# Solenoid_and_Flasher_Driver.net
KiCad netlist of a schematic drawn in Altium Designer
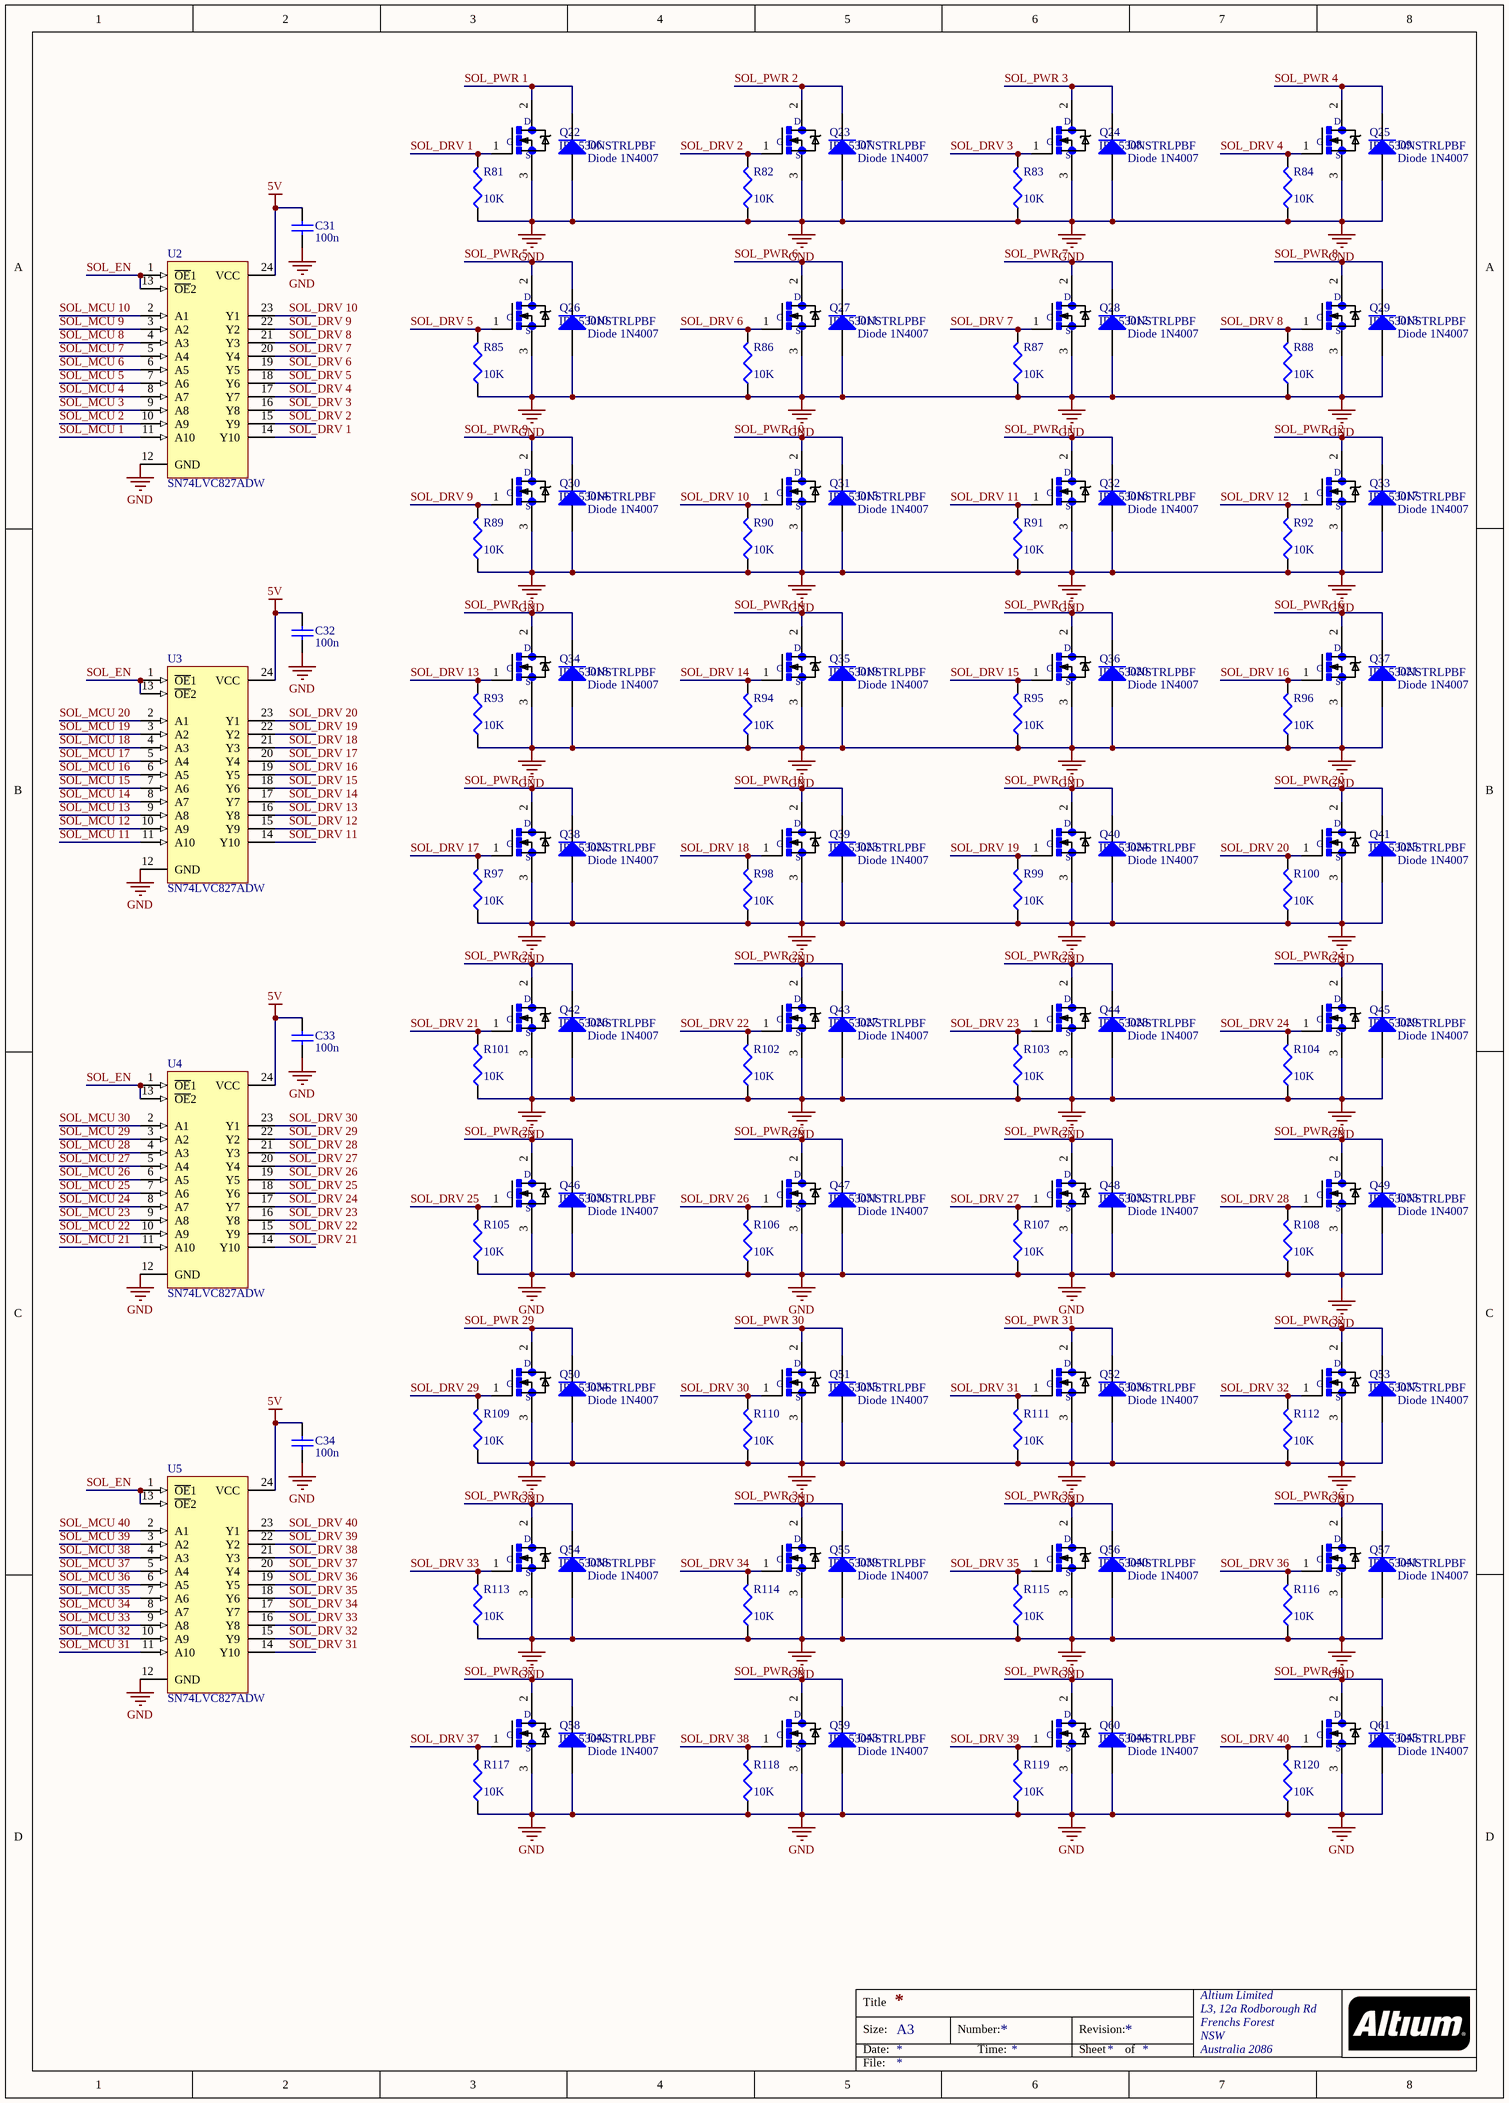
[diagram p0: Solenoid and Flasher Driver.SchDoc]

(export (version "E")
  (design (tool "Eeschema 10.0.6"))
  (components
    (comp (ref "C31")
      (value "100n")
      (footprint "0805C-GENERIC")
      (description "Capacitor (Semiconductor SIM Model)")
      (fields (field (name "Comment") "Cap Semi") (field (name "PUBLISHER") "Altium Limited"))
      (libsource (lib "Miscellaneous Devices") (part "Cap Semi"))
    )
    (comp (ref "C32")
      (value "100n")
      (footprint "0805C-GENERIC")
      (description "Capacitor (Semiconductor SIM Model)")
      (fields (field (name "Comment") "Cap Semi") (field (name "PUBLISHER") "Altium Limited"))
      (libsource (lib "Miscellaneous Devices") (part "Cap Semi"))
    )
    (comp (ref "C33")
      (value "100n")
      (footprint "0805C-GENERIC")
      (description "Capacitor (Semiconductor SIM Model)")
      (fields (field (name "Comment") "Cap Semi") (field (name "PUBLISHER") "Altium Limited"))
      (libsource (lib "Miscellaneous Devices") (part "Cap Semi"))
    )
    (comp (ref "C34")
      (value "100n")
      (footprint "0805C-GENERIC")
      (description "Capacitor (Semiconductor SIM Model)")
      (fields (field (name "Comment") "Cap Semi") (field (name "PUBLISHER") "Altium Limited"))
      (libsource (lib "Miscellaneous Devices") (part "Cap Semi"))
    )
    (comp (ref "D6")
      (value "Diode 1N4007")
      (footprint "DO-41")
      (description "1 Amp General Purpose Rectifier")
      (fields (field (name "PUBLISHER") "Altium Limited"))
      (libsource (lib "Miscellaneous Devices") (part "Diode 1N4007"))
    )
    (comp (ref "D7")
      (value "Diode 1N4007")
      (footprint "DO-41")
      (description "1 Amp General Purpose Rectifier")
      (fields (field (name "PUBLISHER") "Altium Limited"))
      (libsource (lib "Miscellaneous Devices") (part "Diode 1N4007"))
    )
    (comp (ref "D8")
      (value "Diode 1N4007")
      (footprint "DO-41")
      (description "1 Amp General Purpose Rectifier")
      (fields (field (name "PUBLISHER") "Altium Limited"))
      (libsource (lib "Miscellaneous Devices") (part "Diode 1N4007"))
    )
    (comp (ref "D9")
      (value "Diode 1N4007")
      (footprint "DO-41")
      (description "1 Amp General Purpose Rectifier")
      (fields (field (name "PUBLISHER") "Altium Limited"))
      (libsource (lib "Miscellaneous Devices") (part "Diode 1N4007"))
    )
    (comp (ref "D10")
      (value "Diode 1N4007")
      (footprint "DO-41")
      (description "1 Amp General Purpose Rectifier")
      (fields (field (name "PUBLISHER") "Altium Limited"))
      (libsource (lib "Miscellaneous Devices") (part "Diode 1N4007"))
    )
    (comp (ref "D11")
      (value "Diode 1N4007")
      (footprint "DO-41")
      (description "1 Amp General Purpose Rectifier")
      (fields (field (name "PUBLISHER") "Altium Limited"))
      (libsource (lib "Miscellaneous Devices") (part "Diode 1N4007"))
    )
    (comp (ref "D12")
      (value "Diode 1N4007")
      (footprint "DO-41")
      (description "1 Amp General Purpose Rectifier")
      (fields (field (name "PUBLISHER") "Altium Limited"))
      (libsource (lib "Miscellaneous Devices") (part "Diode 1N4007"))
    )
    (comp (ref "D13")
      (value "Diode 1N4007")
      (footprint "DO-41")
      (description "1 Amp General Purpose Rectifier")
      (fields (field (name "PUBLISHER") "Altium Limited"))
      (libsource (lib "Miscellaneous Devices") (part "Diode 1N4007"))
    )
    (comp (ref "D14")
      (value "Diode 1N4007")
      (footprint "DO-41")
      (description "1 Amp General Purpose Rectifier")
      (fields (field (name "PUBLISHER") "Altium Limited"))
      (libsource (lib "Miscellaneous Devices") (part "Diode 1N4007"))
    )
    (comp (ref "D15")
      (value "Diode 1N4007")
      (footprint "DO-41")
      (description "1 Amp General Purpose Rectifier")
      (fields (field (name "PUBLISHER") "Altium Limited"))
      (libsource (lib "Miscellaneous Devices") (part "Diode 1N4007"))
    )
    (comp (ref "D16")
      (value "Diode 1N4007")
      (footprint "DO-41")
      (description "1 Amp General Purpose Rectifier")
      (fields (field (name "PUBLISHER") "Altium Limited"))
      (libsource (lib "Miscellaneous Devices") (part "Diode 1N4007"))
    )
    (comp (ref "D17")
      (value "Diode 1N4007")
      (footprint "DO-41")
      (description "1 Amp General Purpose Rectifier")
      (fields (field (name "PUBLISHER") "Altium Limited"))
      (libsource (lib "Miscellaneous Devices") (part "Diode 1N4007"))
    )
    (comp (ref "D18")
      (value "Diode 1N4007")
      (footprint "DO-41")
      (description "1 Amp General Purpose Rectifier")
      (fields (field (name "PUBLISHER") "Altium Limited"))
      (libsource (lib "Miscellaneous Devices") (part "Diode 1N4007"))
    )
    (comp (ref "D19")
      (value "Diode 1N4007")
      (footprint "DO-41")
      (description "1 Amp General Purpose Rectifier")
      (fields (field (name "PUBLISHER") "Altium Limited"))
      (libsource (lib "Miscellaneous Devices") (part "Diode 1N4007"))
    )
    (comp (ref "D20")
      (value "Diode 1N4007")
      (footprint "DO-41")
      (description "1 Amp General Purpose Rectifier")
      (fields (field (name "PUBLISHER") "Altium Limited"))
      (libsource (lib "Miscellaneous Devices") (part "Diode 1N4007"))
    )
    (comp (ref "D21")
      (value "Diode 1N4007")
      (footprint "DO-41")
      (description "1 Amp General Purpose Rectifier")
      (fields (field (name "PUBLISHER") "Altium Limited"))
      (libsource (lib "Miscellaneous Devices") (part "Diode 1N4007"))
    )
    (comp (ref "D22")
      (value "Diode 1N4007")
      (footprint "DO-41")
      (description "1 Amp General Purpose Rectifier")
      (fields (field (name "PUBLISHER") "Altium Limited"))
      (libsource (lib "Miscellaneous Devices") (part "Diode 1N4007"))
    )
    (comp (ref "D23")
      (value "Diode 1N4007")
      (footprint "DO-41")
      (description "1 Amp General Purpose Rectifier")
      (fields (field (name "PUBLISHER") "Altium Limited"))
      (libsource (lib "Miscellaneous Devices") (part "Diode 1N4007"))
    )
    (comp (ref "D24")
      (value "Diode 1N4007")
      (footprint "DO-41")
      (description "1 Amp General Purpose Rectifier")
      (fields (field (name "PUBLISHER") "Altium Limited"))
      (libsource (lib "Miscellaneous Devices") (part "Diode 1N4007"))
    )
    (comp (ref "D25")
      (value "Diode 1N4007")
      (footprint "DO-41")
      (description "1 Amp General Purpose Rectifier")
      (fields (field (name "PUBLISHER") "Altium Limited"))
      (libsource (lib "Miscellaneous Devices") (part "Diode 1N4007"))
    )
    (comp (ref "D26")
      (value "Diode 1N4007")
      (footprint "DO-41")
      (description "1 Amp General Purpose Rectifier")
      (fields (field (name "PUBLISHER") "Altium Limited"))
      (libsource (lib "Miscellaneous Devices") (part "Diode 1N4007"))
    )
    (comp (ref "D27")
      (value "Diode 1N4007")
      (footprint "DO-41")
      (description "1 Amp General Purpose Rectifier")
      (fields (field (name "PUBLISHER") "Altium Limited"))
      (libsource (lib "Miscellaneous Devices") (part "Diode 1N4007"))
    )
    (comp (ref "D28")
      (value "Diode 1N4007")
      (footprint "DO-41")
      (description "1 Amp General Purpose Rectifier")
      (fields (field (name "PUBLISHER") "Altium Limited"))
      (libsource (lib "Miscellaneous Devices") (part "Diode 1N4007"))
    )
    (comp (ref "D29")
      (value "Diode 1N4007")
      (footprint "DO-41")
      (description "1 Amp General Purpose Rectifier")
      (fields (field (name "PUBLISHER") "Altium Limited"))
      (libsource (lib "Miscellaneous Devices") (part "Diode 1N4007"))
    )
    (comp (ref "D30")
      (value "Diode 1N4007")
      (footprint "DO-41")
      (description "1 Amp General Purpose Rectifier")
      (fields (field (name "PUBLISHER") "Altium Limited"))
      (libsource (lib "Miscellaneous Devices") (part "Diode 1N4007"))
    )
    (comp (ref "D31")
      (value "Diode 1N4007")
      (footprint "DO-41")
      (description "1 Amp General Purpose Rectifier")
      (fields (field (name "PUBLISHER") "Altium Limited"))
      (libsource (lib "Miscellaneous Devices") (part "Diode 1N4007"))
    )
    (comp (ref "D32")
      (value "Diode 1N4007")
      (footprint "DO-41")
      (description "1 Amp General Purpose Rectifier")
      (fields (field (name "PUBLISHER") "Altium Limited"))
      (libsource (lib "Miscellaneous Devices") (part "Diode 1N4007"))
    )
    (comp (ref "D33")
      (value "Diode 1N4007")
      (footprint "DO-41")
      (description "1 Amp General Purpose Rectifier")
      (fields (field (name "PUBLISHER") "Altium Limited"))
      (libsource (lib "Miscellaneous Devices") (part "Diode 1N4007"))
    )
    (comp (ref "D34")
      (value "Diode 1N4007")
      (footprint "DO-41")
      (description "1 Amp General Purpose Rectifier")
      (fields (field (name "PUBLISHER") "Altium Limited"))
      (libsource (lib "Miscellaneous Devices") (part "Diode 1N4007"))
    )
    (comp (ref "D35")
      (value "Diode 1N4007")
      (footprint "DO-41")
      (description "1 Amp General Purpose Rectifier")
      (fields (field (name "PUBLISHER") "Altium Limited"))
      (libsource (lib "Miscellaneous Devices") (part "Diode 1N4007"))
    )
    (comp (ref "D36")
      (value "Diode 1N4007")
      (footprint "DO-41")
      (description "1 Amp General Purpose Rectifier")
      (fields (field (name "PUBLISHER") "Altium Limited"))
      (libsource (lib "Miscellaneous Devices") (part "Diode 1N4007"))
    )
    (comp (ref "D37")
      (value "Diode 1N4007")
      (footprint "DO-41")
      (description "1 Amp General Purpose Rectifier")
      (fields (field (name "PUBLISHER") "Altium Limited"))
      (libsource (lib "Miscellaneous Devices") (part "Diode 1N4007"))
    )
    (comp (ref "D38")
      (value "Diode 1N4007")
      (footprint "DO-41")
      (description "1 Amp General Purpose Rectifier")
      (fields (field (name "PUBLISHER") "Altium Limited"))
      (libsource (lib "Miscellaneous Devices") (part "Diode 1N4007"))
    )
    (comp (ref "D39")
      (value "Diode 1N4007")
      (footprint "DO-41")
      (description "1 Amp General Purpose Rectifier")
      (fields (field (name "PUBLISHER") "Altium Limited"))
      (libsource (lib "Miscellaneous Devices") (part "Diode 1N4007"))
    )
    (comp (ref "D40")
      (value "Diode 1N4007")
      (footprint "DO-41")
      (description "1 Amp General Purpose Rectifier")
      (fields (field (name "PUBLISHER") "Altium Limited"))
      (libsource (lib "Miscellaneous Devices") (part "Diode 1N4007"))
    )
    (comp (ref "D41")
      (value "Diode 1N4007")
      (footprint "DO-41")
      (description "1 Amp General Purpose Rectifier")
      (fields (field (name "PUBLISHER") "Altium Limited"))
      (libsource (lib "Miscellaneous Devices") (part "Diode 1N4007"))
    )
    (comp (ref "D42")
      (value "Diode 1N4007")
      (footprint "DO-41")
      (description "1 Amp General Purpose Rectifier")
      (fields (field (name "PUBLISHER") "Altium Limited"))
      (libsource (lib "Miscellaneous Devices") (part "Diode 1N4007"))
    )
    (comp (ref "D43")
      (value "Diode 1N4007")
      (footprint "DO-41")
      (description "1 Amp General Purpose Rectifier")
      (fields (field (name "PUBLISHER") "Altium Limited"))
      (libsource (lib "Miscellaneous Devices") (part "Diode 1N4007"))
    )
    (comp (ref "D44")
      (value "Diode 1N4007")
      (footprint "DO-41")
      (description "1 Amp General Purpose Rectifier")
      (fields (field (name "PUBLISHER") "Altium Limited"))
      (libsource (lib "Miscellaneous Devices") (part "Diode 1N4007"))
    )
    (comp (ref "D45")
      (value "Diode 1N4007")
      (footprint "DO-41")
      (description "1 Amp General Purpose Rectifier")
      (fields (field (name "PUBLISHER") "Altium Limited"))
      (libsource (lib "Miscellaneous Devices") (part "Diode 1N4007"))
    )
    (comp (ref "Q22")
      (value "IRL530NSTRLPBF")
      (footprint "TO-220AB")
      (description "MOSFET N-CH 100V 17A D2PAK")
      (fields (field (name "MF") "Infineon"))
      (libsource (lib "IRL530NSTRLPBF") (part "IRL530NSTRLPBF"))
    )
    (comp (ref "Q23")
      (value "IRL530NSTRLPBF")
      (footprint "TO-220AB")
      (description "MOSFET N-CH 100V 17A D2PAK")
      (fields (field (name "MF") "Infineon"))
      (libsource (lib "IRL530NSTRLPBF") (part "IRL530NSTRLPBF"))
    )
    (comp (ref "Q24")
      (value "IRL530NSTRLPBF")
      (footprint "TO-220AB")
      (description "MOSFET N-CH 100V 17A D2PAK")
      (fields (field (name "MF") "Infineon"))
      (libsource (lib "IRL530NSTRLPBF") (part "IRL530NSTRLPBF"))
    )
    (comp (ref "Q25")
      (value "IRL530NSTRLPBF")
      (footprint "TO-220AB")
      (description "MOSFET N-CH 100V 17A D2PAK")
      (fields (field (name "MF") "Infineon"))
      (libsource (lib "IRL530NSTRLPBF") (part "IRL530NSTRLPBF"))
    )
    (comp (ref "Q26")
      (value "IRL530NSTRLPBF")
      (footprint "TO-220AB")
      (description "MOSFET N-CH 100V 17A D2PAK")
      (fields (field (name "MF") "Infineon"))
      (libsource (lib "IRL530NSTRLPBF") (part "IRL530NSTRLPBF"))
    )
    (comp (ref "Q27")
      (value "IRL530NSTRLPBF")
      (footprint "TO-220AB")
      (description "MOSFET N-CH 100V 17A D2PAK")
      (fields (field (name "MF") "Infineon"))
      (libsource (lib "IRL530NSTRLPBF") (part "IRL530NSTRLPBF"))
    )
    (comp (ref "Q28")
      (value "IRL530NSTRLPBF")
      (footprint "TO-220AB")
      (description "MOSFET N-CH 100V 17A D2PAK")
      (fields (field (name "MF") "Infineon"))
      (libsource (lib "IRL530NSTRLPBF") (part "IRL530NSTRLPBF"))
    )
    (comp (ref "Q29")
      (value "IRL530NSTRLPBF")
      (footprint "TO-220AB")
      (description "MOSFET N-CH 100V 17A D2PAK")
      (fields (field (name "MF") "Infineon"))
      (libsource (lib "IRL530NSTRLPBF") (part "IRL530NSTRLPBF"))
    )
    (comp (ref "Q30")
      (value "IRL530NSTRLPBF")
      (footprint "TO-220AB")
      (description "MOSFET N-CH 100V 17A D2PAK")
      (fields (field (name "MF") "Infineon"))
      (libsource (lib "IRL530NSTRLPBF") (part "IRL530NSTRLPBF"))
    )
    (comp (ref "Q31")
      (value "IRL530NSTRLPBF")
      (footprint "TO-220AB")
      (description "MOSFET N-CH 100V 17A D2PAK")
      (fields (field (name "MF") "Infineon"))
      (libsource (lib "IRL530NSTRLPBF") (part "IRL530NSTRLPBF"))
    )
    (comp (ref "Q32")
      (value "IRL530NSTRLPBF")
      (footprint "TO-220AB")
      (description "MOSFET N-CH 100V 17A D2PAK")
      (fields (field (name "MF") "Infineon"))
      (libsource (lib "IRL530NSTRLPBF") (part "IRL530NSTRLPBF"))
    )
    (comp (ref "Q33")
      (value "IRL530NSTRLPBF")
      (footprint "TO-220AB")
      (description "MOSFET N-CH 100V 17A D2PAK")
      (fields (field (name "MF") "Infineon"))
      (libsource (lib "IRL530NSTRLPBF") (part "IRL530NSTRLPBF"))
    )
    (comp (ref "Q34")
      (value "IRL530NSTRLPBF")
      (footprint "TO-220AB")
      (description "MOSFET N-CH 100V 17A D2PAK")
      (fields (field (name "MF") "Infineon"))
      (libsource (lib "IRL530NSTRLPBF") (part "IRL530NSTRLPBF"))
    )
    (comp (ref "Q35")
      (value "IRL530NSTRLPBF")
      (footprint "TO-220AB")
      (description "MOSFET N-CH 100V 17A D2PAK")
      (fields (field (name "MF") "Infineon"))
      (libsource (lib "IRL530NSTRLPBF") (part "IRL530NSTRLPBF"))
    )
    (comp (ref "Q36")
      (value "IRL530NSTRLPBF")
      (footprint "TO-220AB")
      (description "MOSFET N-CH 100V 17A D2PAK")
      (fields (field (name "MF") "Infineon"))
      (libsource (lib "IRL530NSTRLPBF") (part "IRL530NSTRLPBF"))
    )
    (comp (ref "Q37")
      (value "IRL530NSTRLPBF")
      (footprint "TO-220AB")
      (description "MOSFET N-CH 100V 17A D2PAK")
      (fields (field (name "MF") "Infineon"))
      (libsource (lib "IRL530NSTRLPBF") (part "IRL530NSTRLPBF"))
    )
    (comp (ref "Q38")
      (value "IRL530NSTRLPBF")
      (footprint "TO-220AB")
      (description "MOSFET N-CH 100V 17A D2PAK")
      (fields (field (name "MF") "Infineon"))
      (libsource (lib "IRL530NSTRLPBF") (part "IRL530NSTRLPBF"))
    )
    (comp (ref "Q39")
      (value "IRL530NSTRLPBF")
      (footprint "TO-220AB")
      (description "MOSFET N-CH 100V 17A D2PAK")
      (fields (field (name "MF") "Infineon"))
      (libsource (lib "IRL530NSTRLPBF") (part "IRL530NSTRLPBF"))
    )
    (comp (ref "Q40")
      (value "IRL530NSTRLPBF")
      (footprint "TO-220AB")
      (description "MOSFET N-CH 100V 17A D2PAK")
      (fields (field (name "MF") "Infineon"))
      (libsource (lib "IRL530NSTRLPBF") (part "IRL530NSTRLPBF"))
    )
    (comp (ref "Q41")
      (value "IRL530NSTRLPBF")
      (footprint "TO-220AB")
      (description "MOSFET N-CH 100V 17A D2PAK")
      (fields (field (name "MF") "Infineon"))
      (libsource (lib "IRL530NSTRLPBF") (part "IRL530NSTRLPBF"))
    )
    (comp (ref "Q42")
      (value "IRL530NSTRLPBF")
      (footprint "TO-220AB")
      (description "MOSFET N-CH 100V 17A D2PAK")
      (fields (field (name "MF") "Infineon"))
      (libsource (lib "IRL530NSTRLPBF") (part "IRL530NSTRLPBF"))
    )
    (comp (ref "Q43")
      (value "IRL530NSTRLPBF")
      (footprint "TO-220AB")
      (description "MOSFET N-CH 100V 17A D2PAK")
      (fields (field (name "MF") "Infineon"))
      (libsource (lib "IRL530NSTRLPBF") (part "IRL530NSTRLPBF"))
    )
    (comp (ref "Q44")
      (value "IRL530NSTRLPBF")
      (footprint "TO-220AB")
      (description "MOSFET N-CH 100V 17A D2PAK")
      (fields (field (name "MF") "Infineon"))
      (libsource (lib "IRL530NSTRLPBF") (part "IRL530NSTRLPBF"))
    )
    (comp (ref "Q45")
      (value "IRL530NSTRLPBF")
      (footprint "TO-220AB")
      (description "MOSFET N-CH 100V 17A D2PAK")
      (fields (field (name "MF") "Infineon"))
      (libsource (lib "IRL530NSTRLPBF") (part "IRL530NSTRLPBF"))
    )
    (comp (ref "Q46")
      (value "IRL530NSTRLPBF")
      (footprint "TO-220AB")
      (description "MOSFET N-CH 100V 17A D2PAK")
      (fields (field (name "MF") "Infineon"))
      (libsource (lib "IRL530NSTRLPBF") (part "IRL530NSTRLPBF"))
    )
    (comp (ref "Q47")
      (value "IRL530NSTRLPBF")
      (footprint "TO-220AB")
      (description "MOSFET N-CH 100V 17A D2PAK")
      (fields (field (name "MF") "Infineon"))
      (libsource (lib "IRL530NSTRLPBF") (part "IRL530NSTRLPBF"))
    )
    (comp (ref "Q48")
      (value "IRL530NSTRLPBF")
      (footprint "TO-220AB")
      (description "MOSFET N-CH 100V 17A D2PAK")
      (fields (field (name "MF") "Infineon"))
      (libsource (lib "IRL530NSTRLPBF") (part "IRL530NSTRLPBF"))
    )
    (comp (ref "Q49")
      (value "IRL530NSTRLPBF")
      (footprint "TO-220AB")
      (description "MOSFET N-CH 100V 17A D2PAK")
      (fields (field (name "MF") "Infineon"))
      (libsource (lib "IRL530NSTRLPBF") (part "IRL530NSTRLPBF"))
    )
    (comp (ref "Q50")
      (value "IRL530NSTRLPBF")
      (footprint "TO-220AB")
      (description "MOSFET N-CH 100V 17A D2PAK")
      (fields (field (name "MF") "Infineon"))
      (libsource (lib "IRL530NSTRLPBF") (part "IRL530NSTRLPBF"))
    )
    (comp (ref "Q51")
      (value "IRL530NSTRLPBF")
      (footprint "TO-220AB")
      (description "MOSFET N-CH 100V 17A D2PAK")
      (fields (field (name "MF") "Infineon"))
      (libsource (lib "IRL530NSTRLPBF") (part "IRL530NSTRLPBF"))
    )
    (comp (ref "Q52")
      (value "IRL530NSTRLPBF")
      (footprint "TO-220AB")
      (description "MOSFET N-CH 100V 17A D2PAK")
      (fields (field (name "MF") "Infineon"))
      (libsource (lib "IRL530NSTRLPBF") (part "IRL530NSTRLPBF"))
    )
    (comp (ref "Q53")
      (value "IRL530NSTRLPBF")
      (footprint "TO-220AB")
      (description "MOSFET N-CH 100V 17A D2PAK")
      (fields (field (name "MF") "Infineon"))
      (libsource (lib "IRL530NSTRLPBF") (part "IRL530NSTRLPBF"))
    )
    (comp (ref "Q54")
      (value "IRL530NSTRLPBF")
      (footprint "TO-220AB")
      (description "MOSFET N-CH 100V 17A D2PAK")
      (fields (field (name "MF") "Infineon"))
      (libsource (lib "IRL530NSTRLPBF") (part "IRL530NSTRLPBF"))
    )
    (comp (ref "Q55")
      (value "IRL530NSTRLPBF")
      (footprint "TO-220AB")
      (description "MOSFET N-CH 100V 17A D2PAK")
      (fields (field (name "MF") "Infineon"))
      (libsource (lib "IRL530NSTRLPBF") (part "IRL530NSTRLPBF"))
    )
    (comp (ref "Q56")
      (value "IRL530NSTRLPBF")
      (footprint "TO-220AB")
      (description "MOSFET N-CH 100V 17A D2PAK")
      (fields (field (name "MF") "Infineon"))
      (libsource (lib "IRL530NSTRLPBF") (part "IRL530NSTRLPBF"))
    )
    (comp (ref "Q57")
      (value "IRL530NSTRLPBF")
      (footprint "TO-220AB")
      (description "MOSFET N-CH 100V 17A D2PAK")
      (fields (field (name "MF") "Infineon"))
      (libsource (lib "IRL530NSTRLPBF") (part "IRL530NSTRLPBF"))
    )
    (comp (ref "Q58")
      (value "IRL530NSTRLPBF")
      (footprint "TO-220AB")
      (description "MOSFET N-CH 100V 17A D2PAK")
      (fields (field (name "MF") "Infineon"))
      (libsource (lib "IRL530NSTRLPBF") (part "IRL530NSTRLPBF"))
    )
    (comp (ref "Q59")
      (value "IRL530NSTRLPBF")
      (footprint "TO-220AB")
      (description "MOSFET N-CH 100V 17A D2PAK")
      (fields (field (name "MF") "Infineon"))
      (libsource (lib "IRL530NSTRLPBF") (part "IRL530NSTRLPBF"))
    )
    (comp (ref "Q60")
      (value "IRL530NSTRLPBF")
      (footprint "TO-220AB")
      (description "MOSFET N-CH 100V 17A D2PAK")
      (fields (field (name "MF") "Infineon"))
      (libsource (lib "IRL530NSTRLPBF") (part "IRL530NSTRLPBF"))
    )
    (comp (ref "Q61")
      (value "IRL530NSTRLPBF")
      (footprint "TO-220AB")
      (description "MOSFET N-CH 100V 17A D2PAK")
      (fields (field (name "MF") "Infineon"))
      (libsource (lib "IRL530NSTRLPBF") (part "IRL530NSTRLPBF"))
    )
    (comp (ref "R81")
      (value "10K")
      (footprint "0805R-GENERIC")
      (description "Resistor")
      (fields (field (name "Comment") "Res3") (field (name "PUBLISHER") "Altium Limited"))
      (libsource (lib "Miscellaneous Devices") (part "Res3"))
    )
    (comp (ref "R82")
      (value "10K")
      (footprint "0805R-GENERIC")
      (description "Resistor")
      (fields (field (name "Comment") "Res3") (field (name "PUBLISHER") "Altium Limited"))
      (libsource (lib "Miscellaneous Devices") (part "Res3"))
    )
    (comp (ref "R83")
      (value "10K")
      (footprint "0805R-GENERIC")
      (description "Resistor")
      (fields (field (name "Comment") "Res3") (field (name "PUBLISHER") "Altium Limited"))
      (libsource (lib "Miscellaneous Devices") (part "Res3"))
    )
    (comp (ref "R84")
      (value "10K")
      (footprint "0805R-GENERIC")
      (description "Resistor")
      (fields (field (name "Comment") "Res3") (field (name "PUBLISHER") "Altium Limited"))
      (libsource (lib "Miscellaneous Devices") (part "Res3"))
    )
    (comp (ref "R85")
      (value "10K")
      (footprint "0805R-GENERIC")
      (description "Resistor")
      (fields (field (name "Comment") "Res3") (field (name "PUBLISHER") "Altium Limited"))
      (libsource (lib "Miscellaneous Devices") (part "Res3"))
    )
    (comp (ref "R86")
      (value "10K")
      (footprint "0805R-GENERIC")
      (description "Resistor")
      (fields (field (name "Comment") "Res3") (field (name "PUBLISHER") "Altium Limited"))
      (libsource (lib "Miscellaneous Devices") (part "Res3"))
    )
    (comp (ref "R87")
      (value "10K")
      (footprint "0805R-GENERIC")
      (description "Resistor")
      (fields (field (name "Comment") "Res3") (field (name "PUBLISHER") "Altium Limited"))
      (libsource (lib "Miscellaneous Devices") (part "Res3"))
    )
    (comp (ref "R88")
      (value "10K")
      (footprint "0805R-GENERIC")
      (description "Resistor")
      (fields (field (name "Comment") "Res3") (field (name "PUBLISHER") "Altium Limited"))
      (libsource (lib "Miscellaneous Devices") (part "Res3"))
    )
    (comp (ref "R89")
      (value "10K")
      (footprint "0805R-GENERIC")
      (description "Resistor")
      (fields (field (name "Comment") "Res3") (field (name "PUBLISHER") "Altium Limited"))
      (libsource (lib "Miscellaneous Devices") (part "Res3"))
    )
    (comp (ref "R90")
      (value "10K")
      (footprint "0805R-GENERIC")
      (description "Resistor")
      (fields (field (name "Comment") "Res3") (field (name "PUBLISHER") "Altium Limited"))
      (libsource (lib "Miscellaneous Devices") (part "Res3"))
    )
    (comp (ref "R91")
      (value "10K")
      (footprint "0805R-GENERIC")
      (description "Resistor")
      (fields (field (name "Comment") "Res3") (field (name "PUBLISHER") "Altium Limited"))
      (libsource (lib "Miscellaneous Devices") (part "Res3"))
    )
    (comp (ref "R92")
      (value "10K")
      (footprint "0805R-GENERIC")
      (description "Resistor")
      (fields (field (name "Comment") "Res3") (field (name "PUBLISHER") "Altium Limited"))
      (libsource (lib "Miscellaneous Devices") (part "Res3"))
    )
    (comp (ref "R93")
      (value "10K")
      (footprint "0805R-GENERIC")
      (description "Resistor")
      (fields (field (name "Comment") "Res3") (field (name "PUBLISHER") "Altium Limited"))
      (libsource (lib "Miscellaneous Devices") (part "Res3"))
    )
    (comp (ref "R94")
      (value "10K")
      (footprint "0805R-GENERIC")
      (description "Resistor")
      (fields (field (name "Comment") "Res3") (field (name "PUBLISHER") "Altium Limited"))
      (libsource (lib "Miscellaneous Devices") (part "Res3"))
    )
    (comp (ref "R95")
      (value "10K")
      (footprint "0805R-GENERIC")
      (description "Resistor")
      (fields (field (name "Comment") "Res3") (field (name "PUBLISHER") "Altium Limited"))
      (libsource (lib "Miscellaneous Devices") (part "Res3"))
    )
    (comp (ref "R96")
      (value "10K")
      (footprint "0805R-GENERIC")
      (description "Resistor")
      (fields (field (name "Comment") "Res3") (field (name "PUBLISHER") "Altium Limited"))
      (libsource (lib "Miscellaneous Devices") (part "Res3"))
    )
    (comp (ref "R97")
      (value "10K")
      (footprint "0805R-GENERIC")
      (description "Resistor")
      (fields (field (name "Comment") "Res3") (field (name "PUBLISHER") "Altium Limited"))
      (libsource (lib "Miscellaneous Devices") (part "Res3"))
    )
    (comp (ref "R98")
      (value "10K")
      (footprint "0805R-GENERIC")
      (description "Resistor")
      (fields (field (name "Comment") "Res3") (field (name "PUBLISHER") "Altium Limited"))
      (libsource (lib "Miscellaneous Devices") (part "Res3"))
    )
    (comp (ref "R99")
      (value "10K")
      (footprint "0805R-GENERIC")
      (description "Resistor")
      (fields (field (name "Comment") "Res3") (field (name "PUBLISHER") "Altium Limited"))
      (libsource (lib "Miscellaneous Devices") (part "Res3"))
    )
    (comp (ref "R100")
      (value "10K")
      (footprint "0805R-GENERIC")
      (description "Resistor")
      (fields (field (name "Comment") "Res3") (field (name "PUBLISHER") "Altium Limited"))
      (libsource (lib "Miscellaneous Devices") (part "Res3"))
    )
    (comp (ref "R101")
      (value "10K")
      (footprint "0805R-GENERIC")
      (description "Resistor")
      (fields (field (name "Comment") "Res3") (field (name "PUBLISHER") "Altium Limited"))
      (libsource (lib "Miscellaneous Devices") (part "Res3"))
    )
    (comp (ref "R102")
      (value "10K")
      (footprint "0805R-GENERIC")
      (description "Resistor")
      (fields (field (name "Comment") "Res3") (field (name "PUBLISHER") "Altium Limited"))
      (libsource (lib "Miscellaneous Devices") (part "Res3"))
    )
    (comp (ref "R103")
      (value "10K")
      (footprint "0805R-GENERIC")
      (description "Resistor")
      (fields (field (name "Comment") "Res3") (field (name "PUBLISHER") "Altium Limited"))
      (libsource (lib "Miscellaneous Devices") (part "Res3"))
    )
    (comp (ref "R104")
      (value "10K")
      (footprint "0805R-GENERIC")
      (description "Resistor")
      (fields (field (name "Comment") "Res3") (field (name "PUBLISHER") "Altium Limited"))
      (libsource (lib "Miscellaneous Devices") (part "Res3"))
    )
    (comp (ref "R105")
      (value "10K")
      (footprint "0805R-GENERIC")
      (description "Resistor")
      (fields (field (name "Comment") "Res3") (field (name "PUBLISHER") "Altium Limited"))
      (libsource (lib "Miscellaneous Devices") (part "Res3"))
    )
    (comp (ref "R106")
      (value "10K")
      (footprint "0805R-GENERIC")
      (description "Resistor")
      (fields (field (name "Comment") "Res3") (field (name "PUBLISHER") "Altium Limited"))
      (libsource (lib "Miscellaneous Devices") (part "Res3"))
    )
    (comp (ref "R107")
      (value "10K")
      (footprint "0805R-GENERIC")
      (description "Resistor")
      (fields (field (name "Comment") "Res3") (field (name "PUBLISHER") "Altium Limited"))
      (libsource (lib "Miscellaneous Devices") (part "Res3"))
    )
    (comp (ref "R108")
      (value "10K")
      (footprint "0805R-GENERIC")
      (description "Resistor")
      (fields (field (name "Comment") "Res3") (field (name "PUBLISHER") "Altium Limited"))
      (libsource (lib "Miscellaneous Devices") (part "Res3"))
    )
    (comp (ref "R109")
      (value "10K")
      (footprint "0805R-GENERIC")
      (description "Resistor")
      (fields (field (name "Comment") "Res3") (field (name "PUBLISHER") "Altium Limited"))
      (libsource (lib "Miscellaneous Devices") (part "Res3"))
    )
    (comp (ref "R110")
      (value "10K")
      (footprint "0805R-GENERIC")
      (description "Resistor")
      (fields (field (name "Comment") "Res3") (field (name "PUBLISHER") "Altium Limited"))
      (libsource (lib "Miscellaneous Devices") (part "Res3"))
    )
    (comp (ref "R111")
      (value "10K")
      (footprint "0805R-GENERIC")
      (description "Resistor")
      (fields (field (name "Comment") "Res3") (field (name "PUBLISHER") "Altium Limited"))
      (libsource (lib "Miscellaneous Devices") (part "Res3"))
    )
    (comp (ref "R112")
      (value "10K")
      (footprint "0805R-GENERIC")
      (description "Resistor")
      (fields (field (name "Comment") "Res3") (field (name "PUBLISHER") "Altium Limited"))
      (libsource (lib "Miscellaneous Devices") (part "Res3"))
    )
    (comp (ref "R113")
      (value "10K")
      (footprint "0805R-GENERIC")
      (description "Resistor")
      (fields (field (name "Comment") "Res3") (field (name "PUBLISHER") "Altium Limited"))
      (libsource (lib "Miscellaneous Devices") (part "Res3"))
    )
    (comp (ref "R114")
      (value "10K")
      (footprint "0805R-GENERIC")
      (description "Resistor")
      (fields (field (name "Comment") "Res3") (field (name "PUBLISHER") "Altium Limited"))
      (libsource (lib "Miscellaneous Devices") (part "Res3"))
    )
    (comp (ref "R115")
      (value "10K")
      (footprint "0805R-GENERIC")
      (description "Resistor")
      (fields (field (name "Comment") "Res3") (field (name "PUBLISHER") "Altium Limited"))
      (libsource (lib "Miscellaneous Devices") (part "Res3"))
    )
    (comp (ref "R116")
      (value "10K")
      (footprint "0805R-GENERIC")
      (description "Resistor")
      (fields (field (name "Comment") "Res3") (field (name "PUBLISHER") "Altium Limited"))
      (libsource (lib "Miscellaneous Devices") (part "Res3"))
    )
    (comp (ref "R117")
      (value "10K")
      (footprint "0805R-GENERIC")
      (description "Resistor")
      (fields (field (name "Comment") "Res3") (field (name "PUBLISHER") "Altium Limited"))
      (libsource (lib "Miscellaneous Devices") (part "Res3"))
    )
    (comp (ref "R118")
      (value "10K")
      (footprint "0805R-GENERIC")
      (description "Resistor")
      (fields (field (name "Comment") "Res3") (field (name "PUBLISHER") "Altium Limited"))
      (libsource (lib "Miscellaneous Devices") (part "Res3"))
    )
    (comp (ref "R119")
      (value "10K")
      (footprint "0805R-GENERIC")
      (description "Resistor")
      (fields (field (name "Comment") "Res3") (field (name "PUBLISHER") "Altium Limited"))
      (libsource (lib "Miscellaneous Devices") (part "Res3"))
    )
    (comp (ref "R120")
      (value "10K")
      (footprint "0805R-GENERIC")
      (description "Resistor")
      (fields (field (name "Comment") "Res3") (field (name "PUBLISHER") "Altium Limited"))
      (libsource (lib "Miscellaneous Devices") (part "Res3"))
    )
    (comp (ref "U2")
      (value "SN74LVC827ADW")
      (footprint "SOIC24")
      (description "10-Bit Buffer/Driver with 3-State Outputs")
      (fields (field (name "PUBLISHER") "Altium Limited"))
      (libsource (lib "Texas_Instruments") (part "SN74LVC827ADW"))
    )
    (comp (ref "U3")
      (value "SN74LVC827ADW")
      (footprint "SOIC24")
      (description "10-Bit Buffer/Driver with 3-State Outputs")
      (fields (field (name "PUBLISHER") "Altium Limited"))
      (libsource (lib "Texas_Instruments") (part "SN74LVC827ADW"))
    )
    (comp (ref "U4")
      (value "SN74LVC827ADW")
      (footprint "SOIC24")
      (description "10-Bit Buffer/Driver with 3-State Outputs")
      (fields (field (name "PUBLISHER") "Altium Limited"))
      (libsource (lib "Texas_Instruments") (part "SN74LVC827ADW"))
    )
    (comp (ref "U5")
      (value "SN74LVC827ADW")
      (footprint "SOIC24")
      (description "10-Bit Buffer/Driver with 3-State Outputs")
      (fields (field (name "PUBLISHER") "Altium Limited"))
      (libsource (lib "Texas_Instruments") (part "SN74LVC827ADW"))
    )
  )
  (nets
    (net (code "1") (name "/SOL_DRV 1") (class "Default")
      (node (ref "Q22") (pin "1") (pinfunction "G_1") (pintype "passive"))
      (node (ref "R81") (pin "2") (pinfunction "2_2") (pintype "passive"))
      (node (ref "U2") (pin "14") (pinfunction "Y10_14") (pintype "tri_state"))
    )
    (net (code "2") (name "/SOL_DRV 2") (class "Default")
      (node (ref "Q23") (pin "1") (pinfunction "G_1") (pintype "passive"))
      (node (ref "R82") (pin "2") (pinfunction "2_2") (pintype "passive"))
      (node (ref "U2") (pin "15") (pinfunction "Y9_15") (pintype "tri_state"))
    )
    (net (code "3") (name "/SOL_DRV 3") (class "Default")
      (node (ref "Q24") (pin "1") (pinfunction "G_1") (pintype "passive"))
      (node (ref "R83") (pin "2") (pinfunction "2_2") (pintype "passive"))
      (node (ref "U2") (pin "16") (pinfunction "Y8_16") (pintype "tri_state"))
    )
    (net (code "4") (name "/SOL_DRV 4") (class "Default")
      (node (ref "Q25") (pin "1") (pinfunction "G_1") (pintype "passive"))
      (node (ref "R84") (pin "2") (pinfunction "2_2") (pintype "passive"))
      (node (ref "U2") (pin "17") (pinfunction "Y7_17") (pintype "tri_state"))
    )
    (net (code "5") (name "/SOL_DRV 5") (class "Default")
      (node (ref "Q26") (pin "1") (pinfunction "G_1") (pintype "passive"))
      (node (ref "R85") (pin "2") (pinfunction "2_2") (pintype "passive"))
      (node (ref "U2") (pin "18") (pinfunction "Y6_18") (pintype "tri_state"))
    )
    (net (code "6") (name "/SOL_DRV 6") (class "Default")
      (node (ref "Q27") (pin "1") (pinfunction "G_1") (pintype "passive"))
      (node (ref "R86") (pin "2") (pinfunction "2_2") (pintype "passive"))
      (node (ref "U2") (pin "19") (pinfunction "Y5_19") (pintype "tri_state"))
    )
    (net (code "7") (name "/SOL_DRV 7") (class "Default")
      (node (ref "Q28") (pin "1") (pinfunction "G_1") (pintype "passive"))
      (node (ref "R87") (pin "2") (pinfunction "2_2") (pintype "passive"))
      (node (ref "U2") (pin "20") (pinfunction "Y4_20") (pintype "tri_state"))
    )
    (net (code "8") (name "/SOL_DRV 8") (class "Default")
      (node (ref "Q29") (pin "1") (pinfunction "G_1") (pintype "passive"))
      (node (ref "R88") (pin "2") (pinfunction "2_2") (pintype "passive"))
      (node (ref "U2") (pin "21") (pinfunction "Y3_21") (pintype "tri_state"))
    )
    (net (code "9") (name "/SOL_DRV 9") (class "Default")
      (node (ref "Q30") (pin "1") (pinfunction "G_1") (pintype "passive"))
      (node (ref "R89") (pin "2") (pinfunction "2_2") (pintype "passive"))
      (node (ref "U2") (pin "22") (pinfunction "Y2_22") (pintype "tri_state"))
    )
    (net (code "10") (name "/SOL_DRV 10") (class "Default")
      (node (ref "Q31") (pin "1") (pinfunction "G_1") (pintype "passive"))
      (node (ref "R90") (pin "2") (pinfunction "2_2") (pintype "passive"))
      (node (ref "U2") (pin "23") (pinfunction "Y1_23") (pintype "tri_state"))
    )
    (net (code "11") (name "/SOL_DRV 11") (class "Default")
      (node (ref "Q32") (pin "1") (pinfunction "G_1") (pintype "passive"))
      (node (ref "R91") (pin "2") (pinfunction "2_2") (pintype "passive"))
      (node (ref "U3") (pin "14") (pinfunction "Y10_14") (pintype "tri_state"))
    )
    (net (code "12") (name "/SOL_DRV 12") (class "Default")
      (node (ref "Q33") (pin "1") (pinfunction "G_1") (pintype "passive"))
      (node (ref "R92") (pin "2") (pinfunction "2_2") (pintype "passive"))
      (node (ref "U3") (pin "15") (pinfunction "Y9_15") (pintype "tri_state"))
    )
    (net (code "13") (name "/SOL_DRV 13") (class "Default")
      (node (ref "Q34") (pin "1") (pinfunction "G_1") (pintype "passive"))
      (node (ref "R93") (pin "2") (pinfunction "2_2") (pintype "passive"))
      (node (ref "U3") (pin "16") (pinfunction "Y8_16") (pintype "tri_state"))
    )
    (net (code "14") (name "/SOL_DRV 14") (class "Default")
      (node (ref "Q35") (pin "1") (pinfunction "G_1") (pintype "passive"))
      (node (ref "R94") (pin "2") (pinfunction "2_2") (pintype "passive"))
      (node (ref "U3") (pin "17") (pinfunction "Y7_17") (pintype "tri_state"))
    )
    (net (code "15") (name "/SOL_DRV 15") (class "Default")
      (node (ref "Q36") (pin "1") (pinfunction "G_1") (pintype "passive"))
      (node (ref "R95") (pin "2") (pinfunction "2_2") (pintype "passive"))
      (node (ref "U3") (pin "18") (pinfunction "Y6_18") (pintype "tri_state"))
    )
    (net (code "16") (name "/SOL_DRV 16") (class "Default")
      (node (ref "Q37") (pin "1") (pinfunction "G_1") (pintype "passive"))
      (node (ref "R96") (pin "2") (pinfunction "2_2") (pintype "passive"))
      (node (ref "U3") (pin "19") (pinfunction "Y5_19") (pintype "tri_state"))
    )
    (net (code "17") (name "/SOL_DRV 17") (class "Default")
      (node (ref "Q38") (pin "1") (pinfunction "G_1") (pintype "passive"))
      (node (ref "R97") (pin "2") (pinfunction "2_2") (pintype "passive"))
      (node (ref "U3") (pin "20") (pinfunction "Y4_20") (pintype "tri_state"))
    )
    (net (code "18") (name "/SOL_DRV 18") (class "Default")
      (node (ref "Q39") (pin "1") (pinfunction "G_1") (pintype "passive"))
      (node (ref "R98") (pin "2") (pinfunction "2_2") (pintype "passive"))
      (node (ref "U3") (pin "21") (pinfunction "Y3_21") (pintype "tri_state"))
    )
    (net (code "19") (name "/SOL_DRV 19") (class "Default")
      (node (ref "Q40") (pin "1") (pinfunction "G_1") (pintype "passive"))
      (node (ref "R99") (pin "2") (pinfunction "2_2") (pintype "passive"))
      (node (ref "U3") (pin "22") (pinfunction "Y2_22") (pintype "tri_state"))
    )
    (net (code "20") (name "/SOL_DRV 20") (class "Default")
      (node (ref "Q41") (pin "1") (pinfunction "G_1") (pintype "passive"))
      (node (ref "R100") (pin "2") (pinfunction "2_2") (pintype "passive"))
      (node (ref "U3") (pin "23") (pinfunction "Y1_23") (pintype "tri_state"))
    )
    (net (code "21") (name "/SOL_DRV 21") (class "Default")
      (node (ref "Q42") (pin "1") (pinfunction "G_1") (pintype "passive"))
      (node (ref "R101") (pin "2") (pinfunction "2_2") (pintype "passive"))
      (node (ref "U4") (pin "14") (pinfunction "Y10_14") (pintype "tri_state"))
    )
    (net (code "22") (name "/SOL_DRV 22") (class "Default")
      (node (ref "Q43") (pin "1") (pinfunction "G_1") (pintype "passive"))
      (node (ref "R102") (pin "2") (pinfunction "2_2") (pintype "passive"))
      (node (ref "U4") (pin "15") (pinfunction "Y9_15") (pintype "tri_state"))
    )
    (net (code "23") (name "/SOL_DRV 23") (class "Default")
      (node (ref "Q44") (pin "1") (pinfunction "G_1") (pintype "passive"))
      (node (ref "R103") (pin "2") (pinfunction "2_2") (pintype "passive"))
      (node (ref "U4") (pin "16") (pinfunction "Y8_16") (pintype "tri_state"))
    )
    (net (code "24") (name "/SOL_DRV 24") (class "Default")
      (node (ref "Q45") (pin "1") (pinfunction "G_1") (pintype "passive"))
      (node (ref "R104") (pin "2") (pinfunction "2_2") (pintype "passive"))
      (node (ref "U4") (pin "17") (pinfunction "Y7_17") (pintype "tri_state"))
    )
    (net (code "25") (name "/SOL_DRV 25") (class "Default")
      (node (ref "Q46") (pin "1") (pinfunction "G_1") (pintype "passive"))
      (node (ref "R105") (pin "2") (pinfunction "2_2") (pintype "passive"))
      (node (ref "U4") (pin "18") (pinfunction "Y6_18") (pintype "tri_state"))
    )
    (net (code "26") (name "/SOL_DRV 26") (class "Default")
      (node (ref "Q47") (pin "1") (pinfunction "G_1") (pintype "passive"))
      (node (ref "R106") (pin "2") (pinfunction "2_2") (pintype "passive"))
      (node (ref "U4") (pin "19") (pinfunction "Y5_19") (pintype "tri_state"))
    )
    (net (code "27") (name "/SOL_DRV 27") (class "Default")
      (node (ref "Q48") (pin "1") (pinfunction "G_1") (pintype "passive"))
      (node (ref "R107") (pin "2") (pinfunction "2_2") (pintype "passive"))
      (node (ref "U4") (pin "20") (pinfunction "Y4_20") (pintype "tri_state"))
    )
    (net (code "28") (name "/SOL_DRV 28") (class "Default")
      (node (ref "Q49") (pin "1") (pinfunction "G_1") (pintype "passive"))
      (node (ref "R108") (pin "2") (pinfunction "2_2") (pintype "passive"))
      (node (ref "U4") (pin "21") (pinfunction "Y3_21") (pintype "tri_state"))
    )
    (net (code "29") (name "/SOL_DRV 29") (class "Default")
      (node (ref "Q50") (pin "1") (pinfunction "G_1") (pintype "passive"))
      (node (ref "R109") (pin "2") (pinfunction "2_2") (pintype "passive"))
      (node (ref "U4") (pin "22") (pinfunction "Y2_22") (pintype "tri_state"))
    )
    (net (code "30") (name "/SOL_DRV 30") (class "Default")
      (node (ref "Q51") (pin "1") (pinfunction "G_1") (pintype "passive"))
      (node (ref "R110") (pin "2") (pinfunction "2_2") (pintype "passive"))
      (node (ref "U4") (pin "23") (pinfunction "Y1_23") (pintype "tri_state"))
    )
    (net (code "31") (name "/SOL_DRV 31") (class "Default")
      (node (ref "Q52") (pin "1") (pinfunction "G_1") (pintype "passive"))
      (node (ref "R111") (pin "2") (pinfunction "2_2") (pintype "passive"))
      (node (ref "U5") (pin "14") (pinfunction "Y10_14") (pintype "tri_state"))
    )
    (net (code "32") (name "/SOL_DRV 32") (class "Default")
      (node (ref "Q53") (pin "1") (pinfunction "G_1") (pintype "passive"))
      (node (ref "R112") (pin "2") (pinfunction "2_2") (pintype "passive"))
      (node (ref "U5") (pin "15") (pinfunction "Y9_15") (pintype "tri_state"))
    )
    (net (code "33") (name "/SOL_DRV 33") (class "Default")
      (node (ref "Q54") (pin "1") (pinfunction "G_1") (pintype "passive"))
      (node (ref "R113") (pin "2") (pinfunction "2_2") (pintype "passive"))
      (node (ref "U5") (pin "16") (pinfunction "Y8_16") (pintype "tri_state"))
    )
    (net (code "34") (name "/SOL_DRV 34") (class "Default")
      (node (ref "Q55") (pin "1") (pinfunction "G_1") (pintype "passive"))
      (node (ref "R114") (pin "2") (pinfunction "2_2") (pintype "passive"))
      (node (ref "U5") (pin "17") (pinfunction "Y7_17") (pintype "tri_state"))
    )
    (net (code "35") (name "/SOL_DRV 35") (class "Default")
      (node (ref "Q56") (pin "1") (pinfunction "G_1") (pintype "passive"))
      (node (ref "R115") (pin "2") (pinfunction "2_2") (pintype "passive"))
      (node (ref "U5") (pin "18") (pinfunction "Y6_18") (pintype "tri_state"))
    )
    (net (code "36") (name "/SOL_DRV 36") (class "Default")
      (node (ref "Q57") (pin "1") (pinfunction "G_1") (pintype "passive"))
      (node (ref "R116") (pin "2") (pinfunction "2_2") (pintype "passive"))
      (node (ref "U5") (pin "19") (pinfunction "Y5_19") (pintype "tri_state"))
    )
    (net (code "37") (name "/SOL_DRV 37") (class "Default")
      (node (ref "Q58") (pin "1") (pinfunction "G_1") (pintype "passive"))
      (node (ref "R117") (pin "2") (pinfunction "2_2") (pintype "passive"))
      (node (ref "U5") (pin "20") (pinfunction "Y4_20") (pintype "tri_state"))
    )
    (net (code "38") (name "/SOL_DRV 38") (class "Default")
      (node (ref "Q59") (pin "1") (pinfunction "G_1") (pintype "passive"))
      (node (ref "R118") (pin "2") (pinfunction "2_2") (pintype "passive"))
      (node (ref "U5") (pin "21") (pinfunction "Y3_21") (pintype "tri_state"))
    )
    (net (code "39") (name "/SOL_DRV 39") (class "Default")
      (node (ref "Q60") (pin "1") (pinfunction "G_1") (pintype "passive"))
      (node (ref "R119") (pin "2") (pinfunction "2_2") (pintype "passive"))
      (node (ref "U5") (pin "22") (pinfunction "Y2_22") (pintype "tri_state"))
    )
    (net (code "40") (name "/SOL_DRV 40") (class "Default")
      (node (ref "Q61") (pin "1") (pinfunction "G_1") (pintype "passive"))
      (node (ref "R120") (pin "2") (pinfunction "2_2") (pintype "passive"))
      (node (ref "U5") (pin "23") (pinfunction "Y1_23") (pintype "tri_state"))
    )
    (net (code "41") (name "/SOL_EN") (class "Default")
      (node (ref "U2") (pin "1") (pinfunction "~{OE}1_1") (pintype "input"))
      (node (ref "U2") (pin "13") (pinfunction "~{OE}2_13") (pintype "input"))
      (node (ref "U3") (pin "1") (pinfunction "~{OE}1_1") (pintype "input"))
      (node (ref "U3") (pin "13") (pinfunction "~{OE}2_13") (pintype "input"))
      (node (ref "U4") (pin "1") (pinfunction "~{OE}1_1") (pintype "input"))
      (node (ref "U4") (pin "13") (pinfunction "~{OE}2_13") (pintype "input"))
      (node (ref "U5") (pin "1") (pinfunction "~{OE}1_1") (pintype "input"))
      (node (ref "U5") (pin "13") (pinfunction "~{OE}2_13") (pintype "input"))
    )
    (net (code "42") (name "/SOL_MCU 1") (class "Default")
      (node (ref "U2") (pin "11") (pinfunction "A10_11") (pintype "input"))
    )
    (net (code "43") (name "/SOL_MCU 2") (class "Default")
      (node (ref "U2") (pin "10") (pinfunction "A9_10") (pintype "input"))
    )
    (net (code "44") (name "/SOL_MCU 3") (class "Default")
      (node (ref "U2") (pin "9") (pinfunction "A8_9") (pintype "input"))
    )
    (net (code "45") (name "/SOL_MCU 4") (class "Default")
      (node (ref "U2") (pin "8") (pinfunction "A7_8") (pintype "input"))
    )
    (net (code "46") (name "/SOL_MCU 5") (class "Default")
      (node (ref "U2") (pin "7") (pinfunction "A6_7") (pintype "input"))
    )
    (net (code "47") (name "/SOL_MCU 6") (class "Default")
      (node (ref "U2") (pin "6") (pinfunction "A5_6") (pintype "input"))
    )
    (net (code "48") (name "/SOL_MCU 7") (class "Default")
      (node (ref "U2") (pin "5") (pinfunction "A4_5") (pintype "input"))
    )
    (net (code "49") (name "/SOL_MCU 8") (class "Default")
      (node (ref "U2") (pin "4") (pinfunction "A3_4") (pintype "input"))
    )
    (net (code "50") (name "/SOL_MCU 9") (class "Default")
      (node (ref "U2") (pin "3") (pinfunction "A2_3") (pintype "input"))
    )
    (net (code "51") (name "/SOL_MCU 10") (class "Default")
      (node (ref "U2") (pin "2") (pinfunction "A1_2") (pintype "input"))
    )
    (net (code "52") (name "/SOL_MCU 11") (class "Default")
      (node (ref "U3") (pin "11") (pinfunction "A10_11") (pintype "input"))
    )
    (net (code "53") (name "/SOL_MCU 12") (class "Default")
      (node (ref "U3") (pin "10") (pinfunction "A9_10") (pintype "input"))
    )
    (net (code "54") (name "/SOL_MCU 13") (class "Default")
      (node (ref "U3") (pin "9") (pinfunction "A8_9") (pintype "input"))
    )
    (net (code "55") (name "/SOL_MCU 14") (class "Default")
      (node (ref "U3") (pin "8") (pinfunction "A7_8") (pintype "input"))
    )
    (net (code "56") (name "/SOL_MCU 15") (class "Default")
      (node (ref "U3") (pin "7") (pinfunction "A6_7") (pintype "input"))
    )
    (net (code "57") (name "/SOL_MCU 16") (class "Default")
      (node (ref "U3") (pin "6") (pinfunction "A5_6") (pintype "input"))
    )
    (net (code "58") (name "/SOL_MCU 17") (class "Default")
      (node (ref "U3") (pin "5") (pinfunction "A4_5") (pintype "input"))
    )
    (net (code "59") (name "/SOL_MCU 18") (class "Default")
      (node (ref "U3") (pin "4") (pinfunction "A3_4") (pintype "input"))
    )
    (net (code "60") (name "/SOL_MCU 19") (class "Default")
      (node (ref "U3") (pin "3") (pinfunction "A2_3") (pintype "input"))
    )
    (net (code "61") (name "/SOL_MCU 20") (class "Default")
      (node (ref "U3") (pin "2") (pinfunction "A1_2") (pintype "input"))
    )
    (net (code "62") (name "/SOL_MCU 21") (class "Default")
      (node (ref "U4") (pin "11") (pinfunction "A10_11") (pintype "input"))
    )
    (net (code "63") (name "/SOL_MCU 22") (class "Default")
      (node (ref "U4") (pin "10") (pinfunction "A9_10") (pintype "input"))
    )
    (net (code "64") (name "/SOL_MCU 23") (class "Default")
      (node (ref "U4") (pin "9") (pinfunction "A8_9") (pintype "input"))
    )
    (net (code "65") (name "/SOL_MCU 24") (class "Default")
      (node (ref "U4") (pin "8") (pinfunction "A7_8") (pintype "input"))
    )
    (net (code "66") (name "/SOL_MCU 25") (class "Default")
      (node (ref "U4") (pin "7") (pinfunction "A6_7") (pintype "input"))
    )
    (net (code "67") (name "/SOL_MCU 26") (class "Default")
      (node (ref "U4") (pin "6") (pinfunction "A5_6") (pintype "input"))
    )
    (net (code "68") (name "/SOL_MCU 27") (class "Default")
      (node (ref "U4") (pin "5") (pinfunction "A4_5") (pintype "input"))
    )
    (net (code "69") (name "/SOL_MCU 28") (class "Default")
      (node (ref "U4") (pin "4") (pinfunction "A3_4") (pintype "input"))
    )
    (net (code "70") (name "/SOL_MCU 29") (class "Default")
      (node (ref "U4") (pin "3") (pinfunction "A2_3") (pintype "input"))
    )
    (net (code "71") (name "/SOL_MCU 30") (class "Default")
      (node (ref "U4") (pin "2") (pinfunction "A1_2") (pintype "input"))
    )
    (net (code "72") (name "/SOL_MCU 31") (class "Default")
      (node (ref "U5") (pin "11") (pinfunction "A10_11") (pintype "input"))
    )
    (net (code "73") (name "/SOL_MCU 32") (class "Default")
      (node (ref "U5") (pin "10") (pinfunction "A9_10") (pintype "input"))
    )
    (net (code "74") (name "/SOL_MCU 33") (class "Default")
      (node (ref "U5") (pin "9") (pinfunction "A8_9") (pintype "input"))
    )
    (net (code "75") (name "/SOL_MCU 34") (class "Default")
      (node (ref "U5") (pin "8") (pinfunction "A7_8") (pintype "input"))
    )
    (net (code "76") (name "/SOL_MCU 35") (class "Default")
      (node (ref "U5") (pin "7") (pinfunction "A6_7") (pintype "input"))
    )
    (net (code "77") (name "/SOL_MCU 36") (class "Default")
      (node (ref "U5") (pin "6") (pinfunction "A5_6") (pintype "input"))
    )
    (net (code "78") (name "/SOL_MCU 37") (class "Default")
      (node (ref "U5") (pin "5") (pinfunction "A4_5") (pintype "input"))
    )
    (net (code "79") (name "/SOL_MCU 38") (class "Default")
      (node (ref "U5") (pin "4") (pinfunction "A3_4") (pintype "input"))
    )
    (net (code "80") (name "/SOL_MCU 39") (class "Default")
      (node (ref "U5") (pin "3") (pinfunction "A2_3") (pintype "input"))
    )
    (net (code "81") (name "/SOL_MCU 40") (class "Default")
      (node (ref "U5") (pin "2") (pinfunction "A1_2") (pintype "input"))
    )
    (net (code "82") (name "/SOL_PWR 1") (class "Default")
      (node (ref "D6") (pin "2") (pinfunction "K_2") (pintype "passive"))
      (node (ref "Q22") (pin "2") (pinfunction "D_2") (pintype "passive"))
    )
    (net (code "83") (name "/SOL_PWR 2") (class "Default")
      (node (ref "D7") (pin "2") (pinfunction "K_2") (pintype "passive"))
      (node (ref "Q23") (pin "2") (pinfunction "D_2") (pintype "passive"))
    )
    (net (code "84") (name "/SOL_PWR 3") (class "Default")
      (node (ref "D8") (pin "2") (pinfunction "K_2") (pintype "passive"))
      (node (ref "Q24") (pin "2") (pinfunction "D_2") (pintype "passive"))
    )
    (net (code "85") (name "/SOL_PWR 4") (class "Default")
      (node (ref "D9") (pin "2") (pinfunction "K_2") (pintype "passive"))
      (node (ref "Q25") (pin "2") (pinfunction "D_2") (pintype "passive"))
    )
    (net (code "86") (name "/SOL_PWR 5") (class "Default")
      (node (ref "D10") (pin "2") (pinfunction "K_2") (pintype "passive"))
      (node (ref "Q26") (pin "2") (pinfunction "D_2") (pintype "passive"))
    )
    (net (code "87") (name "/SOL_PWR 6") (class "Default")
      (node (ref "D11") (pin "2") (pinfunction "K_2") (pintype "passive"))
      (node (ref "Q27") (pin "2") (pinfunction "D_2") (pintype "passive"))
    )
    (net (code "88") (name "/SOL_PWR 7") (class "Default")
      (node (ref "D12") (pin "2") (pinfunction "K_2") (pintype "passive"))
      (node (ref "Q28") (pin "2") (pinfunction "D_2") (pintype "passive"))
    )
    (net (code "89") (name "/SOL_PWR 8") (class "Default")
      (node (ref "D13") (pin "2") (pinfunction "K_2") (pintype "passive"))
      (node (ref "Q29") (pin "2") (pinfunction "D_2") (pintype "passive"))
    )
    (net (code "90") (name "/SOL_PWR 9") (class "Default")
      (node (ref "D14") (pin "2") (pinfunction "K_2") (pintype "passive"))
      (node (ref "Q30") (pin "2") (pinfunction "D_2") (pintype "passive"))
    )
    (net (code "91") (name "/SOL_PWR 10") (class "Default")
      (node (ref "D15") (pin "2") (pinfunction "K_2") (pintype "passive"))
      (node (ref "Q31") (pin "2") (pinfunction "D_2") (pintype "passive"))
    )
    (net (code "92") (name "/SOL_PWR 11") (class "Default")
      (node (ref "D16") (pin "2") (pinfunction "K_2") (pintype "passive"))
      (node (ref "Q32") (pin "2") (pinfunction "D_2") (pintype "passive"))
    )
    (net (code "93") (name "/SOL_PWR 12") (class "Default")
      (node (ref "D17") (pin "2") (pinfunction "K_2") (pintype "passive"))
      (node (ref "Q33") (pin "2") (pinfunction "D_2") (pintype "passive"))
    )
    (net (code "94") (name "/SOL_PWR 13") (class "Default")
      (node (ref "D18") (pin "2") (pinfunction "K_2") (pintype "passive"))
      (node (ref "Q34") (pin "2") (pinfunction "D_2") (pintype "passive"))
    )
    (net (code "95") (name "/SOL_PWR 14") (class "Default")
      (node (ref "D19") (pin "2") (pinfunction "K_2") (pintype "passive"))
      (node (ref "Q35") (pin "2") (pinfunction "D_2") (pintype "passive"))
    )
    (net (code "96") (name "/SOL_PWR 15") (class "Default")
      (node (ref "D20") (pin "2") (pinfunction "K_2") (pintype "passive"))
      (node (ref "Q36") (pin "2") (pinfunction "D_2") (pintype "passive"))
    )
    (net (code "97") (name "/SOL_PWR 16") (class "Default")
      (node (ref "D21") (pin "2") (pinfunction "K_2") (pintype "passive"))
      (node (ref "Q37") (pin "2") (pinfunction "D_2") (pintype "passive"))
    )
    (net (code "98") (name "/SOL_PWR 17") (class "Default")
      (node (ref "D22") (pin "2") (pinfunction "K_2") (pintype "passive"))
      (node (ref "Q38") (pin "2") (pinfunction "D_2") (pintype "passive"))
    )
    (net (code "99") (name "/SOL_PWR 18") (class "Default")
      (node (ref "D23") (pin "2") (pinfunction "K_2") (pintype "passive"))
      (node (ref "Q39") (pin "2") (pinfunction "D_2") (pintype "passive"))
    )
    (net (code "100") (name "/SOL_PWR 19") (class "Default")
      (node (ref "D24") (pin "2") (pinfunction "K_2") (pintype "passive"))
      (node (ref "Q40") (pin "2") (pinfunction "D_2") (pintype "passive"))
    )
    (net (code "101") (name "/SOL_PWR 20") (class "Default")
      (node (ref "D25") (pin "2") (pinfunction "K_2") (pintype "passive"))
      (node (ref "Q41") (pin "2") (pinfunction "D_2") (pintype "passive"))
    )
    (net (code "102") (name "/SOL_PWR 21") (class "Default")
      (node (ref "D26") (pin "2") (pinfunction "K_2") (pintype "passive"))
      (node (ref "Q42") (pin "2") (pinfunction "D_2") (pintype "passive"))
    )
    (net (code "103") (name "/SOL_PWR 22") (class "Default")
      (node (ref "D27") (pin "2") (pinfunction "K_2") (pintype "passive"))
      (node (ref "Q43") (pin "2") (pinfunction "D_2") (pintype "passive"))
    )
    (net (code "104") (name "/SOL_PWR 23") (class "Default")
      (node (ref "D28") (pin "2") (pinfunction "K_2") (pintype "passive"))
      (node (ref "Q44") (pin "2") (pinfunction "D_2") (pintype "passive"))
    )
    (net (code "105") (name "/SOL_PWR 24") (class "Default")
      (node (ref "D29") (pin "2") (pinfunction "K_2") (pintype "passive"))
      (node (ref "Q45") (pin "2") (pinfunction "D_2") (pintype "passive"))
    )
    (net (code "106") (name "/SOL_PWR 25") (class "Default")
      (node (ref "D30") (pin "2") (pinfunction "K_2") (pintype "passive"))
      (node (ref "Q46") (pin "2") (pinfunction "D_2") (pintype "passive"))
    )
    (net (code "107") (name "/SOL_PWR 26") (class "Default")
      (node (ref "D31") (pin "2") (pinfunction "K_2") (pintype "passive"))
      (node (ref "Q47") (pin "2") (pinfunction "D_2") (pintype "passive"))
    )
    (net (code "108") (name "/SOL_PWR 27") (class "Default")
      (node (ref "D32") (pin "2") (pinfunction "K_2") (pintype "passive"))
      (node (ref "Q48") (pin "2") (pinfunction "D_2") (pintype "passive"))
    )
    (net (code "109") (name "/SOL_PWR 28") (class "Default")
      (node (ref "D33") (pin "2") (pinfunction "K_2") (pintype "passive"))
      (node (ref "Q49") (pin "2") (pinfunction "D_2") (pintype "passive"))
    )
    (net (code "110") (name "/SOL_PWR 29") (class "Default")
      (node (ref "D34") (pin "2") (pinfunction "K_2") (pintype "passive"))
      (node (ref "Q50") (pin "2") (pinfunction "D_2") (pintype "passive"))
    )
    (net (code "111") (name "/SOL_PWR 30") (class "Default")
      (node (ref "D35") (pin "2") (pinfunction "K_2") (pintype "passive"))
      (node (ref "Q51") (pin "2") (pinfunction "D_2") (pintype "passive"))
    )
    (net (code "112") (name "/SOL_PWR 31") (class "Default")
      (node (ref "D36") (pin "2") (pinfunction "K_2") (pintype "passive"))
      (node (ref "Q52") (pin "2") (pinfunction "D_2") (pintype "passive"))
    )
    (net (code "113") (name "/SOL_PWR 32") (class "Default")
      (node (ref "D37") (pin "2") (pinfunction "K_2") (pintype "passive"))
      (node (ref "Q53") (pin "2") (pinfunction "D_2") (pintype "passive"))
    )
    (net (code "114") (name "/SOL_PWR 33") (class "Default")
      (node (ref "D38") (pin "2") (pinfunction "K_2") (pintype "passive"))
      (node (ref "Q54") (pin "2") (pinfunction "D_2") (pintype "passive"))
    )
    (net (code "115") (name "/SOL_PWR 34") (class "Default")
      (node (ref "D39") (pin "2") (pinfunction "K_2") (pintype "passive"))
      (node (ref "Q55") (pin "2") (pinfunction "D_2") (pintype "passive"))
    )
    (net (code "116") (name "/SOL_PWR 35") (class "Default")
      (node (ref "D40") (pin "2") (pinfunction "K_2") (pintype "passive"))
      (node (ref "Q56") (pin "2") (pinfunction "D_2") (pintype "passive"))
    )
    (net (code "117") (name "/SOL_PWR 36") (class "Default")
      (node (ref "D41") (pin "2") (pinfunction "K_2") (pintype "passive"))
      (node (ref "Q57") (pin "2") (pinfunction "D_2") (pintype "passive"))
    )
    (net (code "118") (name "/SOL_PWR 37") (class "Default")
      (node (ref "D42") (pin "2") (pinfunction "K_2") (pintype "passive"))
      (node (ref "Q58") (pin "2") (pinfunction "D_2") (pintype "passive"))
    )
    (net (code "119") (name "/SOL_PWR 38") (class "Default")
      (node (ref "D43") (pin "2") (pinfunction "K_2") (pintype "passive"))
      (node (ref "Q59") (pin "2") (pinfunction "D_2") (pintype "passive"))
    )
    (net (code "120") (name "/SOL_PWR 39") (class "Default")
      (node (ref "D44") (pin "2") (pinfunction "K_2") (pintype "passive"))
      (node (ref "Q60") (pin "2") (pinfunction "D_2") (pintype "passive"))
    )
    (net (code "121") (name "/SOL_PWR 40") (class "Default")
      (node (ref "D45") (pin "2") (pinfunction "K_2") (pintype "passive"))
      (node (ref "Q61") (pin "2") (pinfunction "D_2") (pintype "passive"))
    )
    (net (code "122") (name "5V") (class "Default")
      (node (ref "C31") (pin "2") (pinfunction "2_2") (pintype "passive"))
      (node (ref "C32") (pin "2") (pinfunction "2_2") (pintype "passive"))
      (node (ref "C33") (pin "2") (pinfunction "2_2") (pintype "passive"))
      (node (ref "C34") (pin "2") (pinfunction "2_2") (pintype "passive"))
      (node (ref "U2") (pin "24") (pinfunction "VCC_24") (pintype "power_in"))
      (node (ref "U3") (pin "24") (pinfunction "VCC_24") (pintype "power_in"))
      (node (ref "U4") (pin "24") (pinfunction "VCC_24") (pintype "power_in"))
      (node (ref "U5") (pin "24") (pinfunction "VCC_24") (pintype "power_in"))
    )
    (net (code "123") (name "GND") (class "Default")
      (node (ref "C31") (pin "1") (pinfunction "1_1") (pintype "passive"))
      (node (ref "C32") (pin "1") (pinfunction "1_1") (pintype "passive"))
      (node (ref "C33") (pin "1") (pinfunction "1_1") (pintype "passive"))
      (node (ref "C34") (pin "1") (pinfunction "1_1") (pintype "passive"))
      (node (ref "D10") (pin "1") (pinfunction "A_1") (pintype "passive"))
      (node (ref "D11") (pin "1") (pinfunction "A_1") (pintype "passive"))
      (node (ref "D12") (pin "1") (pinfunction "A_1") (pintype "passive"))
      (node (ref "D13") (pin "1") (pinfunction "A_1") (pintype "passive"))
      (node (ref "D14") (pin "1") (pinfunction "A_1") (pintype "passive"))
      (node (ref "D15") (pin "1") (pinfunction "A_1") (pintype "passive"))
      (node (ref "D16") (pin "1") (pinfunction "A_1") (pintype "passive"))
      (node (ref "D17") (pin "1") (pinfunction "A_1") (pintype "passive"))
      (node (ref "D18") (pin "1") (pinfunction "A_1") (pintype "passive"))
      (node (ref "D19") (pin "1") (pinfunction "A_1") (pintype "passive"))
      (node (ref "D20") (pin "1") (pinfunction "A_1") (pintype "passive"))
      (node (ref "D21") (pin "1") (pinfunction "A_1") (pintype "passive"))
      (node (ref "D22") (pin "1") (pinfunction "A_1") (pintype "passive"))
      (node (ref "D23") (pin "1") (pinfunction "A_1") (pintype "passive"))
      (node (ref "D24") (pin "1") (pinfunction "A_1") (pintype "passive"))
      (node (ref "D25") (pin "1") (pinfunction "A_1") (pintype "passive"))
      (node (ref "D26") (pin "1") (pinfunction "A_1") (pintype "passive"))
      (node (ref "D27") (pin "1") (pinfunction "A_1") (pintype "passive"))
      (node (ref "D28") (pin "1") (pinfunction "A_1") (pintype "passive"))
      (node (ref "D29") (pin "1") (pinfunction "A_1") (pintype "passive"))
      (node (ref "D30") (pin "1") (pinfunction "A_1") (pintype "passive"))
      (node (ref "D31") (pin "1") (pinfunction "A_1") (pintype "passive"))
      (node (ref "D32") (pin "1") (pinfunction "A_1") (pintype "passive"))
      (node (ref "D33") (pin "1") (pinfunction "A_1") (pintype "passive"))
      (node (ref "D34") (pin "1") (pinfunction "A_1") (pintype "passive"))
      (node (ref "D35") (pin "1") (pinfunction "A_1") (pintype "passive"))
      (node (ref "D36") (pin "1") (pinfunction "A_1") (pintype "passive"))
      (node (ref "D37") (pin "1") (pinfunction "A_1") (pintype "passive"))
      (node (ref "D38") (pin "1") (pinfunction "A_1") (pintype "passive"))
      (node (ref "D39") (pin "1") (pinfunction "A_1") (pintype "passive"))
      (node (ref "D40") (pin "1") (pinfunction "A_1") (pintype "passive"))
      (node (ref "D41") (pin "1") (pinfunction "A_1") (pintype "passive"))
      (node (ref "D42") (pin "1") (pinfunction "A_1") (pintype "passive"))
      (node (ref "D43") (pin "1") (pinfunction "A_1") (pintype "passive"))
      (node (ref "D44") (pin "1") (pinfunction "A_1") (pintype "passive"))
      (node (ref "D45") (pin "1") (pinfunction "A_1") (pintype "passive"))
      (node (ref "D6") (pin "1") (pinfunction "A_1") (pintype "passive"))
      (node (ref "D7") (pin "1") (pinfunction "A_1") (pintype "passive"))
      (node (ref "D8") (pin "1") (pinfunction "A_1") (pintype "passive"))
      (node (ref "D9") (pin "1") (pinfunction "A_1") (pintype "passive"))
      (node (ref "Q22") (pin "3") (pinfunction "S_3") (pintype "passive"))
      (node (ref "Q23") (pin "3") (pinfunction "S_3") (pintype "passive"))
      (node (ref "Q24") (pin "3") (pinfunction "S_3") (pintype "passive"))
      (node (ref "Q25") (pin "3") (pinfunction "S_3") (pintype "passive"))
      (node (ref "Q26") (pin "3") (pinfunction "S_3") (pintype "passive"))
      (node (ref "Q27") (pin "3") (pinfunction "S_3") (pintype "passive"))
      (node (ref "Q28") (pin "3") (pinfunction "S_3") (pintype "passive"))
      (node (ref "Q29") (pin "3") (pinfunction "S_3") (pintype "passive"))
      (node (ref "Q30") (pin "3") (pinfunction "S_3") (pintype "passive"))
      (node (ref "Q31") (pin "3") (pinfunction "S_3") (pintype "passive"))
      (node (ref "Q32") (pin "3") (pinfunction "S_3") (pintype "passive"))
      (node (ref "Q33") (pin "3") (pinfunction "S_3") (pintype "passive"))
      (node (ref "Q34") (pin "3") (pinfunction "S_3") (pintype "passive"))
      (node (ref "Q35") (pin "3") (pinfunction "S_3") (pintype "passive"))
      (node (ref "Q36") (pin "3") (pinfunction "S_3") (pintype "passive"))
      (node (ref "Q37") (pin "3") (pinfunction "S_3") (pintype "passive"))
      (node (ref "Q38") (pin "3") (pinfunction "S_3") (pintype "passive"))
      (node (ref "Q39") (pin "3") (pinfunction "S_3") (pintype "passive"))
      (node (ref "Q40") (pin "3") (pinfunction "S_3") (pintype "passive"))
      (node (ref "Q41") (pin "3") (pinfunction "S_3") (pintype "passive"))
      (node (ref "Q42") (pin "3") (pinfunction "S_3") (pintype "passive"))
      (node (ref "Q43") (pin "3") (pinfunction "S_3") (pintype "passive"))
      (node (ref "Q44") (pin "3") (pinfunction "S_3") (pintype "passive"))
      (node (ref "Q45") (pin "3") (pinfunction "S_3") (pintype "passive"))
      (node (ref "Q46") (pin "3") (pinfunction "S_3") (pintype "passive"))
      (node (ref "Q47") (pin "3") (pinfunction "S_3") (pintype "passive"))
      (node (ref "Q48") (pin "3") (pinfunction "S_3") (pintype "passive"))
      (node (ref "Q49") (pin "3") (pinfunction "S_3") (pintype "passive"))
      (node (ref "Q50") (pin "3") (pinfunction "S_3") (pintype "passive"))
      (node (ref "Q51") (pin "3") (pinfunction "S_3") (pintype "passive"))
      (node (ref "Q52") (pin "3") (pinfunction "S_3") (pintype "passive"))
      (node (ref "Q53") (pin "3") (pinfunction "S_3") (pintype "passive"))
      (node (ref "Q54") (pin "3") (pinfunction "S_3") (pintype "passive"))
      (node (ref "Q55") (pin "3") (pinfunction "S_3") (pintype "passive"))
      (node (ref "Q56") (pin "3") (pinfunction "S_3") (pintype "passive"))
      (node (ref "Q57") (pin "3") (pinfunction "S_3") (pintype "passive"))
      (node (ref "Q58") (pin "3") (pinfunction "S_3") (pintype "passive"))
      (node (ref "Q59") (pin "3") (pinfunction "S_3") (pintype "passive"))
      (node (ref "Q60") (pin "3") (pinfunction "S_3") (pintype "passive"))
      (node (ref "Q61") (pin "3") (pinfunction "S_3") (pintype "passive"))
      (node (ref "R100") (pin "1") (pinfunction "1_1") (pintype "passive"))
      (node (ref "R101") (pin "1") (pinfunction "1_1") (pintype "passive"))
      (node (ref "R102") (pin "1") (pinfunction "1_1") (pintype "passive"))
      (node (ref "R103") (pin "1") (pinfunction "1_1") (pintype "passive"))
      (node (ref "R104") (pin "1") (pinfunction "1_1") (pintype "passive"))
      (node (ref "R105") (pin "1") (pinfunction "1_1") (pintype "passive"))
      (node (ref "R106") (pin "1") (pinfunction "1_1") (pintype "passive"))
      (node (ref "R107") (pin "1") (pinfunction "1_1") (pintype "passive"))
      (node (ref "R108") (pin "1") (pinfunction "1_1") (pintype "passive"))
      (node (ref "R109") (pin "1") (pinfunction "1_1") (pintype "passive"))
      (node (ref "R110") (pin "1") (pinfunction "1_1") (pintype "passive"))
      (node (ref "R111") (pin "1") (pinfunction "1_1") (pintype "passive"))
      (node (ref "R112") (pin "1") (pinfunction "1_1") (pintype "passive"))
      (node (ref "R113") (pin "1") (pinfunction "1_1") (pintype "passive"))
      (node (ref "R114") (pin "1") (pinfunction "1_1") (pintype "passive"))
      (node (ref "R115") (pin "1") (pinfunction "1_1") (pintype "passive"))
      (node (ref "R116") (pin "1") (pinfunction "1_1") (pintype "passive"))
      (node (ref "R117") (pin "1") (pinfunction "1_1") (pintype "passive"))
      (node (ref "R118") (pin "1") (pinfunction "1_1") (pintype "passive"))
      (node (ref "R119") (pin "1") (pinfunction "1_1") (pintype "passive"))
      (node (ref "R120") (pin "1") (pinfunction "1_1") (pintype "passive"))
      (node (ref "R81") (pin "1") (pinfunction "1_1") (pintype "passive"))
      (node (ref "R82") (pin "1") (pinfunction "1_1") (pintype "passive"))
      (node (ref "R83") (pin "1") (pinfunction "1_1") (pintype "passive"))
      (node (ref "R84") (pin "1") (pinfunction "1_1") (pintype "passive"))
      (node (ref "R85") (pin "1") (pinfunction "1_1") (pintype "passive"))
      (node (ref "R86") (pin "1") (pinfunction "1_1") (pintype "passive"))
      (node (ref "R87") (pin "1") (pinfunction "1_1") (pintype "passive"))
      (node (ref "R88") (pin "1") (pinfunction "1_1") (pintype "passive"))
      (node (ref "R89") (pin "1") (pinfunction "1_1") (pintype "passive"))
      (node (ref "R90") (pin "1") (pinfunction "1_1") (pintype "passive"))
      (node (ref "R91") (pin "1") (pinfunction "1_1") (pintype "passive"))
      (node (ref "R92") (pin "1") (pinfunction "1_1") (pintype "passive"))
      (node (ref "R93") (pin "1") (pinfunction "1_1") (pintype "passive"))
      (node (ref "R94") (pin "1") (pinfunction "1_1") (pintype "passive"))
      (node (ref "R95") (pin "1") (pinfunction "1_1") (pintype "passive"))
      (node (ref "R96") (pin "1") (pinfunction "1_1") (pintype "passive"))
      (node (ref "R97") (pin "1") (pinfunction "1_1") (pintype "passive"))
      (node (ref "R98") (pin "1") (pinfunction "1_1") (pintype "passive"))
      (node (ref "R99") (pin "1") (pinfunction "1_1") (pintype "passive"))
      (node (ref "U2") (pin "12") (pinfunction "GND_12") (pintype "power_in"))
      (node (ref "U3") (pin "12") (pinfunction "GND_12") (pintype "power_in"))
      (node (ref "U4") (pin "12") (pinfunction "GND_12") (pintype "power_in"))
      (node (ref "U5") (pin "12") (pinfunction "GND_12") (pintype "power_in"))
    )
  )
)
